# ao.net
KiCad netlist of a schematic drawn in Altium Designer
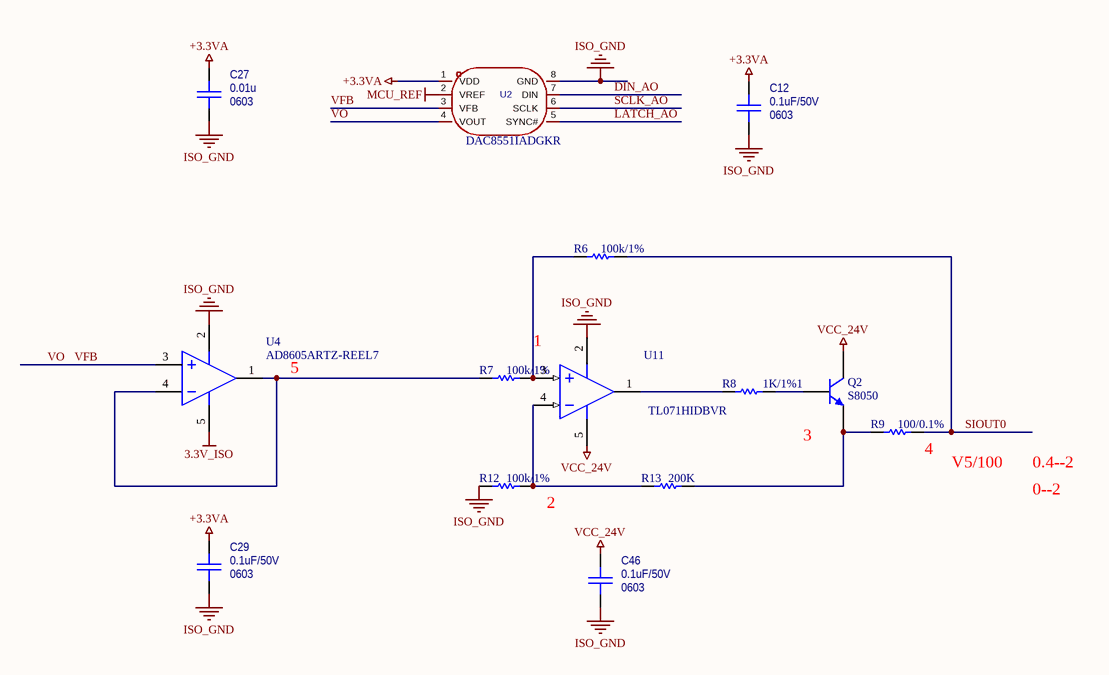
[diagram p0: ao.SchDoc]

(export (version "E")
  (design (tool "Eeschema 10.0.6"))
  (components
    (comp (ref "C12")
      (value "0.1uF/50V")
      (footprint "0603C")
      (description "Capacitor, MLCC")
      (fields (field (name "PACKAGE") "0603"))
      (libsource (lib "Karl") (part "Capacitor_0603"))
    )
    (comp (ref "C27")
      (value "0.01u")
      (footprint "0603C")
      (description "Capacitor, MLCC")
      (fields (field (name "PACKAGE") "0603") (field (name "Comment") "0.01uF/50V"))
      (libsource (lib "Karl") (part "Capacitor_0603"))
    )
    (comp (ref "C29")
      (value "0.1uF/50V")
      (footprint "0603C")
      (description "Capacitor, MLCC")
      (fields (field (name "PACKAGE") "0603"))
      (libsource (lib "Karl") (part "Capacitor_0603"))
    )
    (comp (ref "C46")
      (value "0.1uF/50V")
      (footprint "0603C")
      (description "Capacitor, MLCC")
      (fields (field (name "PACKAGE") "0603"))
      (libsource (lib "Karl") (part "Capacitor_0603"))
    )
    (comp (ref "Q2")
      (value "S8050")
      (footprint "SOT23-3")
      (description "NPN Bipolar Transistor")
      (libsource (lib "Miscellaneous Devices") (part "NPN"))
    )
    (comp (ref "R6")
      (value "100k/1%")
      (footprint "0603R")
      (description "Resistor")
      (libsource (lib "Miscellaneous Devices") (part "Res1"))
    )
    (comp (ref "R7")
      (value "100k/1%")
      (footprint "0603R")
      (description "Resistor")
      (libsource (lib "Miscellaneous Devices") (part "Res1"))
    )
    (comp (ref "R8")
      (value "1K/1%1")
      (footprint "0603R")
      (description "Resistor")
      (libsource (lib "Miscellaneous Devices") (part "Res1"))
    )
    (comp (ref "R9")
      (value "100/0.1%")
      (footprint "0603R")
      (description "Resistor")
      (libsource (lib "Miscellaneous Devices") (part "Res1"))
    )
    (comp (ref "R12")
      (value "100k/1%")
      (footprint "0603R")
      (description "Resistor")
      (libsource (lib "Miscellaneous Devices") (part "Res1"))
    )
    (comp (ref "R13")
      (value "200K")
      (footprint "0603R")
      (description "Resistor")
      (libsource (lib "Miscellaneous Devices") (part "Res1"))
    )
    (comp (ref "U2")
      (value "DAC8551IADGKR")
      (footprint "VSSOP-8_L3.0-W3.0-P0.65-LS5.0-BL")
      (libsource (lib "altium-import") (part "root_0_DAC8551IADGKR_"))
    )
    (comp (ref "U4")
      (value "AD8605ARTZ-REEL7")
      (footprint "sot-23-5")
      (libsource (lib "Schlib1") (part "AD8615"))
    )
    (comp (ref "U11")
      (value "TL071HIDBVR")
      (footprint "DBV0005A_M")
      (libsource (lib "Bogen") (part "TL071HIDBVR"))
    )
  )
  (nets
    (net (code "1") (name "+3.3VA") (class "Default")
      (node (ref "C12") (pin "1") (pinfunction "1_1") (pintype "passive"))
      (node (ref "C27") (pin "1") (pinfunction "1_1") (pintype "passive"))
      (node (ref "C29") (pin "1") (pinfunction "1_1") (pintype "passive"))
      (node (ref "U2") (pin "1") (pinfunction "VDD_1") (pintype "passive"))
    )
    (net (code "2") (name "/DIN_AO") (class "Default")
      (node (ref "U2") (pin "7") (pinfunction "DIN_7") (pintype "passive"))
    )
    (net (code "3") (name "/LATCH_AO") (class "Default")
      (node (ref "U2") (pin "5") (pinfunction "SYNC#_5") (pintype "passive"))
    )
    (net (code "4") (name "/SCLK_AO") (class "Default")
      (node (ref "U2") (pin "6") (pinfunction "SCLK_6") (pintype "passive"))
    )
    (net (code "5") (name "/SIOUT0") (class "Default")
      (node (ref "R6") (pin "2") (pinfunction "2_2") (pintype "passive"))
      (node (ref "R9") (pin "2") (pinfunction "2_2") (pintype "passive"))
    )
    (net (code "6") (name "/VFB") (class "Default")
      (node (ref "U2") (pin "3") (pinfunction "VFB_3") (pintype "passive"))
      (node (ref "U2") (pin "4") (pinfunction "VOUT_4") (pintype "passive"))
      (node (ref "U4") (pin "3") (pinfunction "V+_3") (pintype "power_in"))
    )
    (net (code "7") (name "3.3V_ISO") (class "Default")
      (node (ref "U4") (pin "5") (pinfunction "VCC_5") (pintype "passive"))
    )
    (net (code "8") (name "ISO_GND") (class "Default")
      (node (ref "C12") (pin "2") (pinfunction "2_2") (pintype "passive"))
      (node (ref "C27") (pin "2") (pinfunction "2_2") (pintype "passive"))
      (node (ref "C29") (pin "2") (pinfunction "2_2") (pintype "passive"))
      (node (ref "C46") (pin "2") (pinfunction "2_2") (pintype "passive"))
      (node (ref "R12") (pin "1") (pinfunction "1_1") (pintype "passive"))
      (node (ref "U11") (pin "2") (pinfunction "V-_2") (pintype "power_in"))
      (node (ref "U2") (pin "8") (pinfunction "GND_8") (pintype "passive"))
      (node (ref "U4") (pin "2") (pinfunction "G_2") (pintype "power_in"))
    )
    (net (code "9") (name "MCU_REF") (class "Default")
      (node (ref "U2") (pin "2") (pinfunction "VREF_2") (pintype "passive"))
    )
    (net (code "10") (name "Net-(Q2-B)") (class "Default")
      (node (ref "Q2") (pin "1") (pinfunction "B_1") (pintype "passive"))
      (node (ref "R8") (pin "1") (pinfunction "1_1") (pintype "passive"))
    )
    (net (code "11") (name "Net-(Q2-E)") (class "Default")
      (node (ref "Q2") (pin "2") (pinfunction "E_2") (pintype "passive"))
      (node (ref "R13") (pin "2") (pinfunction "2_2") (pintype "passive"))
      (node (ref "R9") (pin "1") (pinfunction "1_1") (pintype "passive"))
    )
    (net (code "12") (name "Net-(U4-OS_NUL)") (class "Default")
      (node (ref "R7") (pin "1") (pinfunction "1_1") (pintype "passive"))
      (node (ref "U4") (pin "1") (pinfunction "OS_NUL_1") (pintype "passive"))
      (node (ref "U4") (pin "4") (pinfunction "V-_4") (pintype "power_in"))
    )
    (net (code "13") (name "Net-(U11-IN+)") (class "Default")
      (node (ref "R6") (pin "1") (pinfunction "1_1") (pintype "passive"))
      (node (ref "R7") (pin "2") (pinfunction "2_2") (pintype "passive"))
      (node (ref "U11") (pin "3") (pinfunction "IN+_3") (pintype "input"))
    )
    (net (code "14") (name "Net-(U11-IN-)") (class "Default")
      (node (ref "R12") (pin "2") (pinfunction "2_2") (pintype "passive"))
      (node (ref "R13") (pin "1") (pinfunction "1_1") (pintype "passive"))
      (node (ref "U11") (pin "4") (pinfunction "IN-_4") (pintype "input"))
    )
    (net (code "15") (name "Net-(U11-OUT)") (class "Default")
      (node (ref "R8") (pin "2") (pinfunction "2_2") (pintype "passive"))
      (node (ref "U11") (pin "1") (pinfunction "OUT_1") (pintype "tri_state"))
    )
    (net (code "16") (name "VCC_24V") (class "Default")
      (node (ref "C46") (pin "1") (pinfunction "1_1") (pintype "passive"))
      (node (ref "Q2") (pin "3") (pinfunction "C_3") (pintype "passive"))
      (node (ref "U11") (pin "5") (pinfunction "V+_5") (pintype "power_in"))
    )
  )
)
